# SCH_TOP_BOARD.net
KiCad netlist of a schematic drawn in EasyEDA
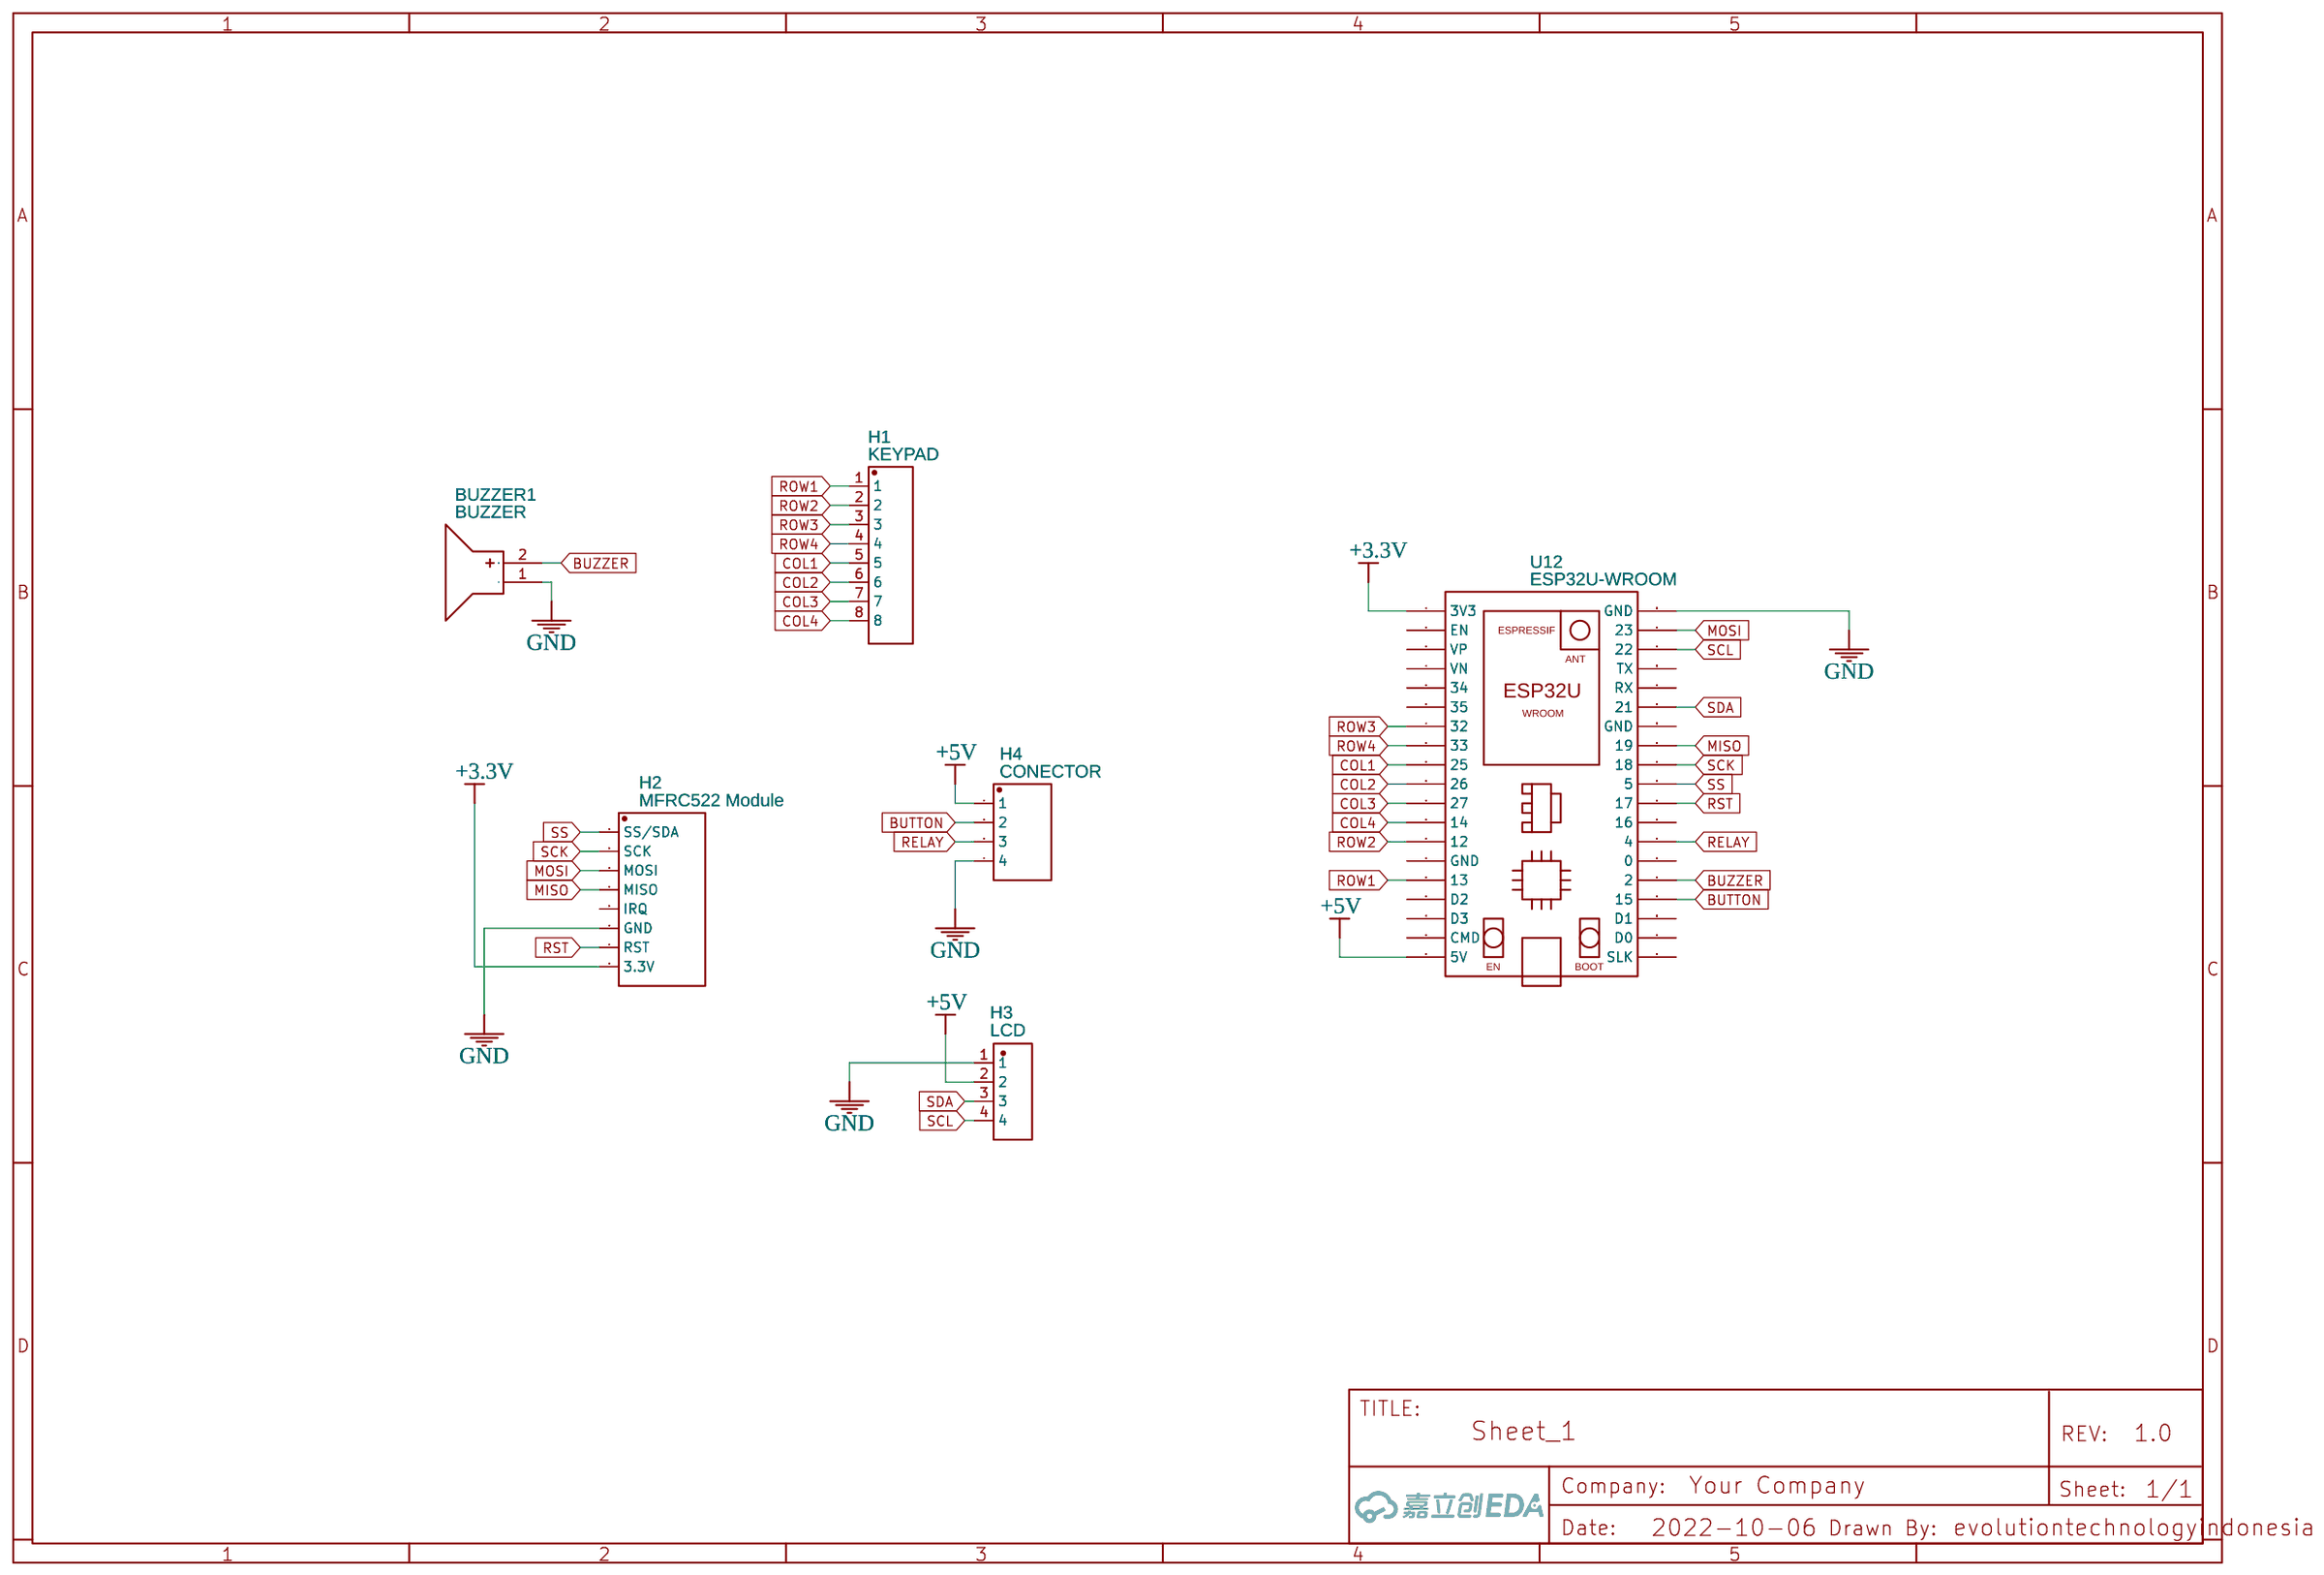
[diagram p0: schematic sheet]

(export (version "E")
  (design (tool "Eeschema 10.0.6"))
  (components
    (comp (ref "BUZZER1")
      (value "BUZZER")
      (fields
        (field (name "BOM_Manufacturer Part") "buzzer")
        (field (name "BOM_Supplier Part") "C9900014030")
      )
      (libsource (lib "") (part "BUZZER"))
    )
    (comp (ref "H1")
      (value "KEYPAD")
      (fields
        (field (name "BOM_Manufacturer Part") "220S-1*8P H=8.5MM Ytype Gold-plated")
        (field (name "BOM_Supplier Part") "C124416")
      )
      (libsource (lib "") (part "220S-1*8P H=8.5MM Ytype Gold-plated"))
    )
    (comp (ref "H2")
      (value "MFRC522 Module")
      (fields (field (name "BOM_Manufacturer Part") "210S-1*8P L=11.6MMGold-plated black"))
      (libsource (lib "") (part "MFRC522 Module"))
    )
    (comp (ref "H3")
      (value "LCD")
      (fields
        (field (name "BOM_Manufacturer Part") "PZ254-1-04-Z-8.5")
        (field (name "BOM_Supplier Part") "C2894927")
      )
      (libsource (lib "") (part "PZ254-1-04-Z-8.5"))
    )
    (comp (ref "H4")
      (value "CONECTOR")
      (fields
        (field (name "BOM_Manufacturer Part") "B-2100S04P-A110")
        (field (name "BOM_Supplier Part") "C124378")
      )
      (libsource (lib "") (part "Header-Male-2.54_1x4"))
    )
    (comp (ref "U12") (value "ESP32U-WROOM") (libsource (lib "") (part "ESP32U-WROOM")))
  )
  (nets
    (net (code "1") (name "+3.3V") (class "Default")
      (node (ref "H2") (pin "8") (pinfunction "3.3V_8") (pintype "unspecified"))
      (node (ref "U12") (pin "1") (pinfunction "3V3_1") (pintype "unspecified"))
    )
    (net (code "2") (name "+5V") (class "Default")
      (node (ref "H3") (pin "2") (pinfunction "2_2") (pintype "unspecified"))
      (node (ref "H4") (pin "1") (pinfunction "1_1") (pintype "unspecified"))
      (node (ref "U12") (pin "19") (pinfunction "5V_19") (pintype "unspecified"))
    )
    (net (code "3") (name "BUTTON") (class "Default")
      (node (ref "H4") (pin "2") (pinfunction "2_2") (pintype "unspecified"))
      (node (ref "U12") (pin "35") (pinfunction "15_35") (pintype "unspecified"))
    )
    (net (code "4") (name "BUZZER") (class "Default")
      (node (ref "BUZZER1") (pin "2") (pinfunction "+_2") (pintype "unspecified"))
      (node (ref "U12") (pin "34") (pinfunction "2_34") (pintype "unspecified"))
    )
    (net (code "5") (name "COL1") (class "Default")
      (node (ref "H1") (pin "5") (pinfunction "5_5") (pintype "unspecified"))
      (node (ref "U12") (pin "9") (pinfunction "25_9") (pintype "unspecified"))
    )
    (net (code "6") (name "COL2") (class "Default")
      (node (ref "H1") (pin "6") (pinfunction "6_6") (pintype "unspecified"))
      (node (ref "U12") (pin "10") (pinfunction "26_10") (pintype "unspecified"))
    )
    (net (code "7") (name "COL3") (class "Default")
      (node (ref "H1") (pin "7") (pinfunction "7_7") (pintype "unspecified"))
      (node (ref "U12") (pin "11") (pinfunction "27_11") (pintype "unspecified"))
    )
    (net (code "8") (name "COL4") (class "Default")
      (node (ref "H1") (pin "8") (pinfunction "8_8") (pintype "unspecified"))
      (node (ref "U12") (pin "12") (pinfunction "14_12") (pintype "unspecified"))
    )
    (net (code "9") (name "GND") (class "Default")
      (node (ref "BUZZER1") (pin "1") (pinfunction "-_1") (pintype "unspecified"))
      (node (ref "H2") (pin "6") (pinfunction "GND_6") (pintype "unspecified"))
      (node (ref "H3") (pin "1") (pinfunction "1_1") (pintype "unspecified"))
      (node (ref "H4") (pin "4") (pinfunction "4_4") (pintype "unspecified"))
      (node (ref "U12") (pin "20") (pinfunction "GND_20") (pintype "unspecified"))
    )
    (net (code "10") (name "MISO") (class "Default")
      (node (ref "H2") (pin "4") (pinfunction "MISO_4") (pintype "unspecified"))
      (node (ref "U12") (pin "27") (pinfunction "19_27") (pintype "unspecified"))
    )
    (net (code "11") (name "MOSI") (class "Default")
      (node (ref "H2") (pin "3") (pinfunction "MOSI_3") (pintype "unspecified"))
      (node (ref "U12") (pin "21") (pinfunction "23_21") (pintype "unspecified"))
    )
    (net (code "12") (name "RELAY") (class "Default")
      (node (ref "H4") (pin "3") (pinfunction "3_3") (pintype "unspecified"))
      (node (ref "U12") (pin "32") (pinfunction "4_32") (pintype "unspecified"))
    )
    (net (code "13") (name "ROW1") (class "Default")
      (node (ref "H1") (pin "1") (pinfunction "1_1") (pintype "unspecified"))
      (node (ref "U12") (pin "15") (pinfunction "13_15") (pintype "unspecified"))
    )
    (net (code "14") (name "ROW2") (class "Default")
      (node (ref "H1") (pin "2") (pinfunction "2_2") (pintype "unspecified"))
      (node (ref "U12") (pin "13") (pinfunction "12_13") (pintype "unspecified"))
    )
    (net (code "15") (name "ROW3") (class "Default")
      (node (ref "H1") (pin "3") (pinfunction "3_3") (pintype "unspecified"))
      (node (ref "U12") (pin "7") (pinfunction "32_7") (pintype "unspecified"))
    )
    (net (code "16") (name "ROW4") (class "Default")
      (node (ref "H1") (pin "4") (pinfunction "4_4") (pintype "unspecified"))
      (node (ref "U12") (pin "8") (pinfunction "33_8") (pintype "unspecified"))
    )
    (net (code "17") (name "RST") (class "Default")
      (node (ref "H2") (pin "7") (pinfunction "RST_7") (pintype "unspecified"))
      (node (ref "U12") (pin "30") (pinfunction "17_30") (pintype "unspecified"))
    )
    (net (code "18") (name "SCK") (class "Default")
      (node (ref "H2") (pin "2") (pinfunction "SCK_2") (pintype "unspecified"))
      (node (ref "U12") (pin "28") (pinfunction "18_28") (pintype "unspecified"))
    )
    (net (code "19") (name "SCL") (class "Default")
      (node (ref "H3") (pin "4") (pinfunction "4_4") (pintype "unspecified"))
      (node (ref "U12") (pin "22") (pinfunction "22_22") (pintype "unspecified"))
    )
    (net (code "20") (name "SDA") (class "Default")
      (node (ref "H3") (pin "3") (pinfunction "3_3") (pintype "unspecified"))
      (node (ref "U12") (pin "25") (pinfunction "21_25") (pintype "unspecified"))
    )
    (net (code "21") (name "SS") (class "Default")
      (node (ref "H2") (pin "1") (pinfunction "SS/SDA_1") (pintype "unspecified"))
      (node (ref "U12") (pin "29") (pinfunction "5_29") (pintype "unspecified"))
    )
    (net (code "22") (name "unconnected-(H2-IRQ-Pad5)") (class "Default")
      (node (ref "H2") (pin "5") (pinfunction "IRQ_5") (pintype "unspecified"))
    )
    (net (code "23") (name "unconnected-(U12-0-Pad33)") (class "Default")
      (node (ref "U12") (pin "33") (pinfunction "0_33") (pintype "unspecified"))
    )
    (net (code "24") (name "unconnected-(U12-16-Pad31)") (class "Default")
      (node (ref "U12") (pin "31") (pinfunction "16_31") (pintype "unspecified"))
    )
    (net (code "25") (name "unconnected-(U12-34-Pad5)") (class "Default")
      (node (ref "U12") (pin "5") (pinfunction "34_5") (pintype "unspecified"))
    )
    (net (code "26") (name "unconnected-(U12-35-Pad6)") (class "Default")
      (node (ref "U12") (pin "6") (pinfunction "35_6") (pintype "unspecified"))
    )
    (net (code "27") (name "unconnected-(U12-CMD-Pad18)") (class "Default")
      (node (ref "U12") (pin "18") (pinfunction "CMD_18") (pintype "unspecified"))
    )
    (net (code "28") (name "unconnected-(U12-D0-Pad37)") (class "Default")
      (node (ref "U12") (pin "37") (pinfunction "D0_37") (pintype "unspecified"))
    )
    (net (code "29") (name "unconnected-(U12-D1-Pad36)") (class "Default")
      (node (ref "U12") (pin "36") (pinfunction "D1_36") (pintype "unspecified"))
    )
    (net (code "30") (name "unconnected-(U12-D2-Pad16)") (class "Default")
      (node (ref "U12") (pin "16") (pinfunction "D2_16") (pintype "unspecified"))
    )
    (net (code "31") (name "unconnected-(U12-D3-Pad17)") (class "Default")
      (node (ref "U12") (pin "17") (pinfunction "D3_17") (pintype "unspecified"))
    )
    (net (code "32") (name "unconnected-(U12-EN-Pad2)") (class "Default")
      (node (ref "U12") (pin "2") (pinfunction "EN_2") (pintype "unspecified"))
    )
    (net (code "33") (name "unconnected-(U12-GND-Pad14)") (class "Default")
      (node (ref "U12") (pin "14") (pinfunction "GND_14") (pintype "unspecified"))
    )
    (net (code "34") (name "unconnected-(U12-GND-Pad26)") (class "Default")
      (node (ref "U12") (pin "26") (pinfunction "GND_26") (pintype "unspecified"))
    )
    (net (code "35") (name "unconnected-(U12-RX-Pad24)") (class "Default")
      (node (ref "U12") (pin "24") (pinfunction "RX_24") (pintype "unspecified"))
    )
    (net (code "36") (name "unconnected-(U12-SLK-Pad38)") (class "Default")
      (node (ref "U12") (pin "38") (pinfunction "SLK_38") (pintype "unspecified"))
    )
    (net (code "37") (name "unconnected-(U12-TX-Pad23)") (class "Default")
      (node (ref "U12") (pin "23") (pinfunction "TX_23") (pintype "unspecified"))
    )
    (net (code "38") (name "unconnected-(U12-VN-Pad4)") (class "Default")
      (node (ref "U12") (pin "4") (pinfunction "VN_4") (pintype "unspecified"))
    )
    (net (code "39") (name "unconnected-(U12-VP-Pad3)") (class "Default")
      (node (ref "U12") (pin "3") (pinfunction "VP_3") (pintype "unspecified"))
    )
  )
)
